# Hypnos_V2_1.net
KiCad netlist of a schematic drawn in EAGLE
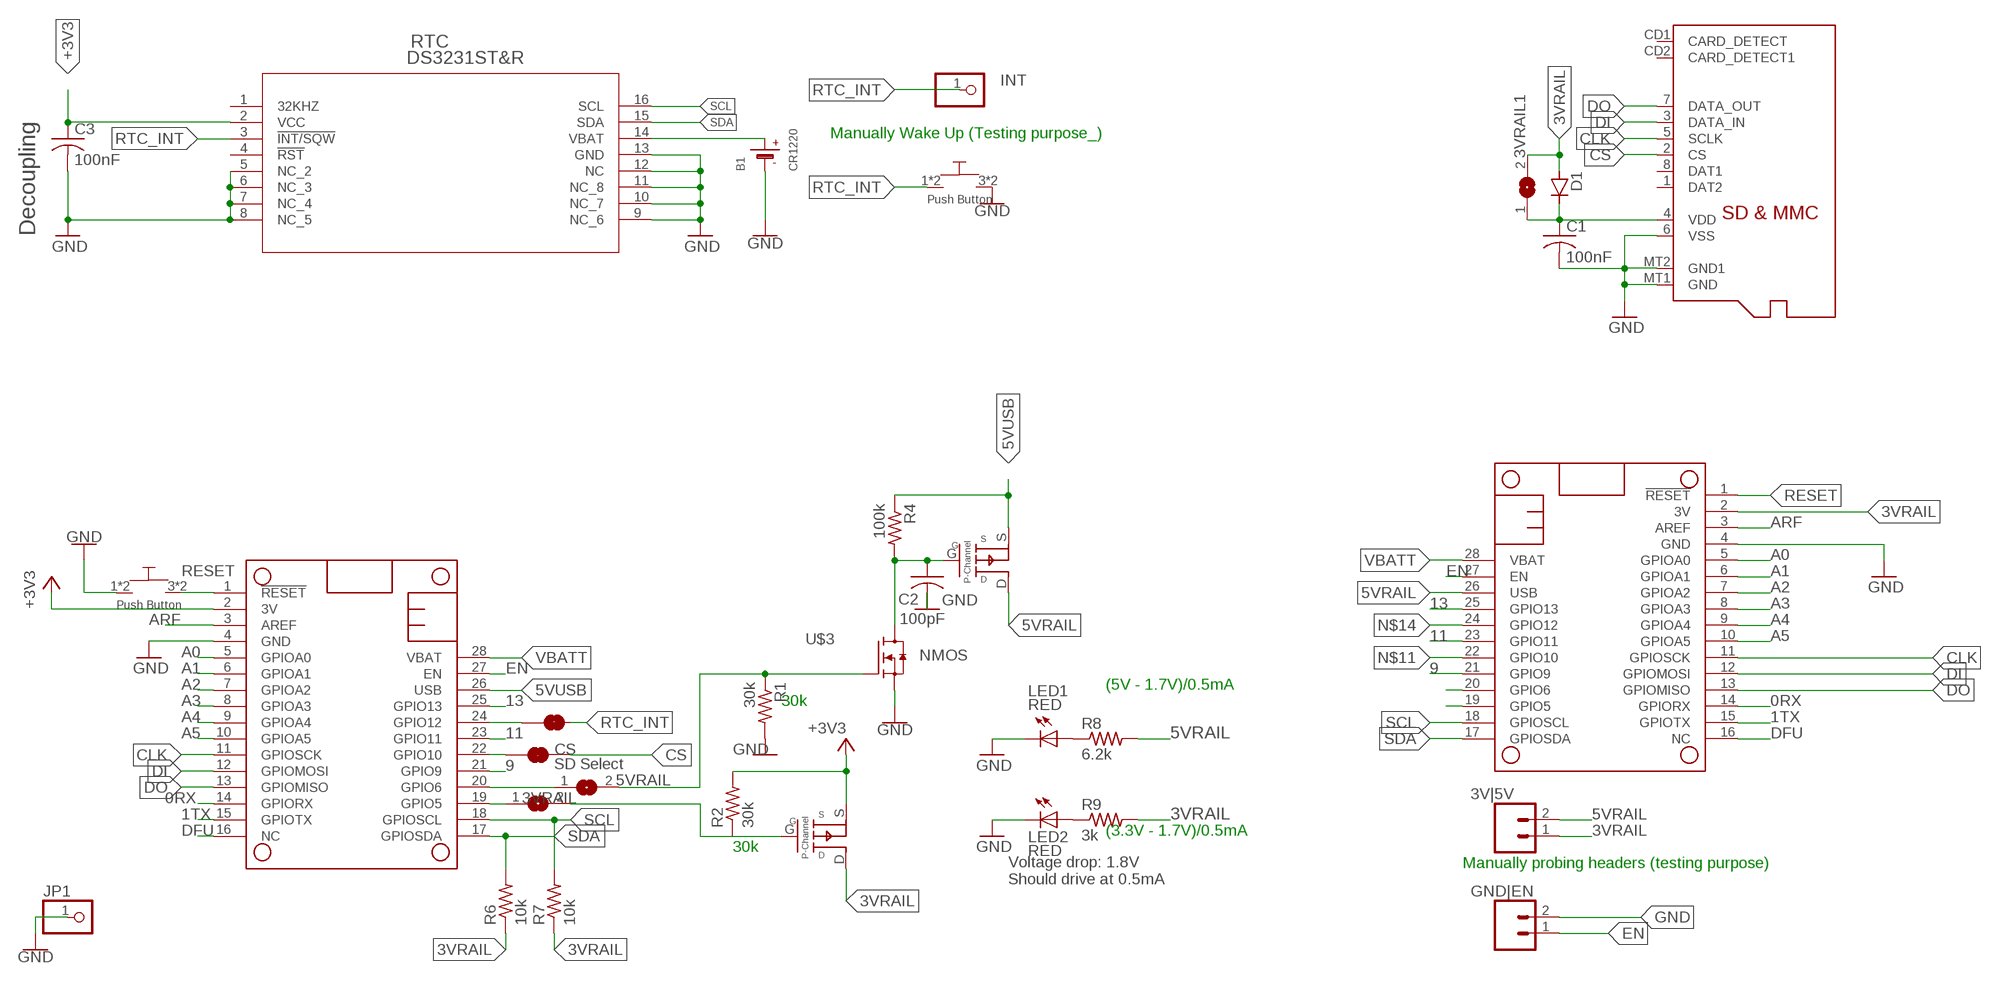
[diagram p0: schematic, sheet 1]

(export (version "E")
  (design (tool "Eeschema 10.0.6"))
  (components
    (comp (ref "3VRAIL")
      (value "SJ")
      (footprint "eagle-import:SJ")
      (libsource (lib "eagle-import") (part "SJ"))
    )
    (comp (ref "3VRAIL1")
      (value "SJ")
      (footprint "eagle-import:SJ")
      (libsource (lib "eagle-import") (part "SJ"))
    )
    (comp (ref "3V|5V")
      (value "CONN_021X02_NO_SILK")
      (footprint "eagle-import:1X02_NO_SILK")
      (libsource (lib "eagle-import") (part "CONN_021X02_NO_SILK"))
    )
    (comp (ref "5VRAIL")
      (value "SJ")
      (footprint "eagle-import:SJ")
      (libsource (lib "eagle-import") (part "SJ"))
    )
    (comp (ref "B1")
      (value "CR1220")
      (footprint "eagle-import:CR1220")
      (libsource (lib "eagle-import") (part "BATTERYCR1220_SMT"))
    )
    (comp (ref "C1")
      (value "100nF")
      (footprint "eagle-import:C1206")
      (libsource (lib "eagle-import") (part "C-USC1206"))
    )
    (comp (ref "C2")
      (value "100pF")
      (footprint "eagle-import:C0805")
      (libsource (lib "eagle-import") (part "C-USC0805"))
    )
    (comp (ref "C3")
      (value "100nF")
      (footprint "eagle-import:C1206")
      (libsource (lib "eagle-import") (part "C-USC1206"))
    )
    (comp (ref "CS")
      (value "SD Select")
      (footprint "eagle-import:SMT-JUMPER_2_NC_TRACE_SILK")
      (libsource (lib "eagle-import") (part "JUMPER-SMT_2_NC_TRACE_SILK"))
    )
    (comp (ref "D1")
      (value "D-SOD123")
      (footprint "eagle-import:SOD123")
      (libsource (lib "eagle-import") (part "D-SOD123"))
    )
    (comp (ref "GND|EN")
      (value "CONN_021X02_NO_SILK")
      (footprint "eagle-import:1X02_NO_SILK")
      (libsource (lib "eagle-import") (part "CONN_021X02_NO_SILK"))
    )
    (comp (ref "INT")
      (value "PINHD-1X1CB")
      (footprint "eagle-import:1X01-CLEANBIG")
      (libsource (lib "eagle-import") (part "PINHD-1X1CB"))
    )
    (comp (ref "JP1")
      (value "PINHD-1X1CB")
      (footprint "eagle-import:1X01-CLEANBIG")
      (libsource (lib "eagle-import") (part "PINHD-1X1CB"))
    )
    (comp (ref "LED1")
      (value "RED")
      (footprint "eagle-import:CHIPLED_0805")
      (libsource (lib "eagle-import") (part "LEDCHIPLED_0805"))
    )
    (comp (ref "LED2")
      (value "RED")
      (footprint "eagle-import:CHIPLED_0805")
      (libsource (lib "eagle-import") (part "LEDCHIPLED_0805"))
    )
    (comp (ref "MICROSD")
      (value "MICROSD")
      (footprint "eagle-import:MICROSD")
      (libsource (lib "eagle-import") (part "MICROSD"))
    )
    (comp (ref "MS1")
      (value "FEATHERWING")
      (footprint "eagle-import:FEATHERWING")
      (libsource (lib "eagle-import") (part "powerboard_FEATHERWING"))
    )
    (comp (ref "MS2")
      (value "FEATHERWING")
      (footprint "eagle-import:FEATHERWING")
      (libsource (lib "eagle-import") (part "FEATHERWING"))
    )
    (comp (ref "PMOS1")
      (value "SSM3J3228R")
      (footprint "eagle-import:SOT-23-3")
      (libsource (lib "eagle-import") (part "SSM3J3228R"))
    )
    (comp (ref "PMOS2")
      (value "SSM3J3228R")
      (footprint "eagle-import:SOT-23-3")
      (libsource (lib "eagle-import") (part "SSM3J3228R"))
    )
    (comp (ref "R1")
      (value "30k")
      (footprint "eagle-import:RES_1206")
      (fields
        (field (name "DIGIKEY_PART_NUMBER") "WSLP-.05TR-ND")
        (field (name "MANUFACTURER") "Vishay Dale")
        (field (name "MPN") "WSLP1206R0500FEA")
        (field (name "CREATED_BY") "PCBLayout.com")
      )
      (libsource (lib "eagle-import") (part "WSLP1206R0500FEA"))
    )
    (comp (ref "R2")
      (value "30k")
      (footprint "eagle-import:RES_1206")
      (fields
        (field (name "DIGIKEY_PART_NUMBER") "WSLP-.05TR-ND")
        (field (name "MANUFACTURER") "Vishay Dale")
        (field (name "MPN") "WSLP1206R0500FEA")
        (field (name "CREATED_BY") "PCBLayout.com")
      )
      (libsource (lib "eagle-import") (part "WSLP1206R0500FEA"))
    )
    (comp (ref "R4")
      (value "100k")
      (footprint "eagle-import:RES_1206")
      (fields
        (field (name "DIGIKEY_PART_NUMBER") "WSLP-.05TR-ND")
        (field (name "MANUFACTURER") "Vishay Dale")
        (field (name "MPN") "WSLP1206R0500FEA")
        (field (name "CREATED_BY") "PCBLayout.com")
      )
      (libsource (lib "eagle-import") (part "WSLP1206R0500FEA"))
    )
    (comp (ref "R6")
      (value "10k")
      (footprint "eagle-import:RES_1206")
      (fields
        (field (name "DIGIKEY_PART_NUMBER") "WSLP-.05TR-ND")
        (field (name "MANUFACTURER") "Vishay Dale")
        (field (name "MPN") "WSLP1206R0500FEA")
        (field (name "CREATED_BY") "PCBLayout.com")
      )
      (libsource (lib "eagle-import") (part "WSLP1206R0500FEA"))
    )
    (comp (ref "R7")
      (value "10k")
      (footprint "eagle-import:RES_1206")
      (fields
        (field (name "DIGIKEY_PART_NUMBER") "WSLP-.05TR-ND")
        (field (name "MANUFACTURER") "Vishay Dale")
        (field (name "MPN") "WSLP1206R0500FEA")
        (field (name "CREATED_BY") "PCBLayout.com")
      )
      (libsource (lib "eagle-import") (part "WSLP1206R0500FEA"))
    )
    (comp (ref "R8")
      (value "6.2k")
      (footprint "eagle-import:RES_1206")
      (fields
        (field (name "DIGIKEY_PART_NUMBER") "WSLP-.05TR-ND")
        (field (name "MANUFACTURER") "Vishay Dale")
        (field (name "MPN") "WSLP1206R0500FEA")
        (field (name "CREATED_BY") "PCBLayout.com")
      )
      (libsource (lib "eagle-import") (part "WSLP1206R0500FEA"))
    )
    (comp (ref "R9")
      (value "3k")
      (footprint "eagle-import:RES_1206")
      (fields
        (field (name "DIGIKEY_PART_NUMBER") "WSLP-.05TR-ND")
        (field (name "MANUFACTURER") "Vishay Dale")
        (field (name "MPN") "WSLP1206R0500FEA")
        (field (name "CREATED_BY") "PCBLayout.com")
      )
      (libsource (lib "eagle-import") (part "WSLP1206R0500FEA"))
    )
    (comp (ref "RTC")
      (value "DS3231ST&R")
      (footprint "eagle-import:21-0042B_16")
      (fields (field (name "MANUFACTURER_PART_NUMBER") "DS3231S#T&R"))
      (libsource (lib "eagle-import") (part "DS3231ST&R"))
    )
    (comp (ref "RTC_INT")
      (value "JUMPER-SMT_2_NC_TRACE_SILK")
      (footprint "eagle-import:SMT-JUMPER_2_NC_TRACE_SILK")
      (libsource (lib "eagle-import") (part "JUMPER-SMT_2_NC_TRACE_SILK"))
    )
    (comp (ref "U$1")
      (value "PUSH_BUTTON")
      (footprint "eagle-import:PUSHBUTTON_SMD")
      (libsource (lib "eagle-import") (part "PUSH_BUTTON"))
    )
    (comp (ref "U$2")
      (value "PUSH_BUTTON")
      (footprint "eagle-import:PUSHBUTTON_SMD")
      (libsource (lib "eagle-import") (part "PUSH_BUTTON"))
    )
    (comp (ref "U$3")
      (value "NMOS")
      (footprint "eagle-import:SOT23-S")
      (libsource (lib "eagle-import") (part "NMOS"))
    )
  )
  (nets
    (net (code "1") (name "+3V3") (class "Default")
      (node (ref "C3") (pin "1") (pinfunction "1_1") (pintype "passive"))
      (node (ref "MS2") (pin "2") (pinfunction "3V_2") (pintype "power_in"))
      (node (ref "PMOS2") (pin "S") (pinfunction "S_S") (pintype "bidirectional"))
      (node (ref "R2") (pin "2") (pinfunction "2_2") (pintype "passive"))
      (node (ref "RTC") (pin "2") (pinfunction "VCC_2") (pintype "power_in"))
    )
    (net (code "2") (name "/0RX") (class "Default")
      (node (ref "MS1") (pin "14") (pinfunction "GPIORX_14") (pintype "bidirectional"))
      (node (ref "MS2") (pin "14") (pinfunction "GPIORX_14") (pintype "bidirectional"))
    )
    (net (code "3") (name "/1TX") (class "Default")
      (node (ref "MS1") (pin "15") (pinfunction "GPIOTX_15") (pintype "bidirectional"))
      (node (ref "MS2") (pin "15") (pinfunction "GPIOTX_15") (pintype "bidirectional"))
    )
    (net (code "4") (name "/9") (class "Default")
      (node (ref "MS1") (pin "21") (pinfunction "GPIO9_21") (pintype "bidirectional"))
      (node (ref "MS2") (pin "21") (pinfunction "GPIO9_21") (pintype "bidirectional"))
    )
    (net (code "5") (name "/11") (class "Default")
      (node (ref "MS1") (pin "23") (pinfunction "GPIO11_23") (pintype "bidirectional"))
      (node (ref "MS2") (pin "23") (pinfunction "GPIO11_23") (pintype "bidirectional"))
    )
    (net (code "6") (name "/13") (class "Default")
      (node (ref "MS1") (pin "25") (pinfunction "GPIO13_25") (pintype "bidirectional"))
      (node (ref "MS2") (pin "25") (pinfunction "GPIO13_25") (pintype "bidirectional"))
    )
    (net (code "7") (name "/A0") (class "Default")
      (node (ref "MS1") (pin "5") (pinfunction "GPIOA0_5") (pintype "bidirectional"))
      (node (ref "MS2") (pin "5") (pinfunction "GPIOA0_5") (pintype "bidirectional"))
    )
    (net (code "8") (name "/A1") (class "Default")
      (node (ref "MS1") (pin "6") (pinfunction "GPIOA1_6") (pintype "bidirectional"))
      (node (ref "MS2") (pin "6") (pinfunction "GPIOA1_6") (pintype "bidirectional"))
    )
    (net (code "9") (name "/A2") (class "Default")
      (node (ref "MS1") (pin "7") (pinfunction "GPIOA2_7") (pintype "bidirectional"))
      (node (ref "MS2") (pin "7") (pinfunction "GPIOA2_7") (pintype "bidirectional"))
    )
    (net (code "10") (name "/A3") (class "Default")
      (node (ref "MS1") (pin "8") (pinfunction "GPIOA3_8") (pintype "bidirectional"))
      (node (ref "MS2") (pin "8") (pinfunction "GPIOA3_8") (pintype "bidirectional"))
    )
    (net (code "11") (name "/A4") (class "Default")
      (node (ref "MS1") (pin "9") (pinfunction "GPIOA4_9") (pintype "bidirectional"))
      (node (ref "MS2") (pin "9") (pinfunction "GPIOA4_9") (pintype "bidirectional"))
    )
    (net (code "12") (name "/A5") (class "Default")
      (node (ref "MS1") (pin "10") (pinfunction "GPIOA5_10") (pintype "bidirectional"))
      (node (ref "MS2") (pin "10") (pinfunction "GPIOA5_10") (pintype "bidirectional"))
    )
    (net (code "13") (name "/ARF") (class "Default")
      (node (ref "MS1") (pin "3") (pinfunction "AREF_3") (pintype "passive"))
      (node (ref "MS2") (pin "3") (pinfunction "AREF_3") (pintype "passive"))
    )
    (net (code "14") (name "/DFU") (class "Default")
      (node (ref "MS1") (pin "16") (pinfunction "NC_16") (pintype "passive"))
      (node (ref "MS2") (pin "16") (pinfunction "NC_16") (pintype "passive"))
    )
    (net (code "15") (name "3VRAIL") (class "Default")
      (node (ref "3VRAIL1") (pin "2") (pinfunction "2_2") (pintype "passive"))
      (node (ref "3V|5V") (pin "1") (pinfunction "1_1") (pintype "passive"))
      (node (ref "D1") (pin "2") (pinfunction "A_2") (pintype "passive"))
      (node (ref "MS1") (pin "2") (pinfunction "3V_2") (pintype "power_in"))
      (node (ref "PMOS2") (pin "D") (pinfunction "D_D") (pintype "bidirectional"))
      (node (ref "R6") (pin "1") (pinfunction "1_1") (pintype "passive"))
      (node (ref "R7") (pin "1") (pinfunction "1_1") (pintype "passive"))
      (node (ref "R9") (pin "2") (pinfunction "2_2") (pintype "passive"))
    )
    (net (code "16") (name "5VRAIL") (class "Default")
      (node (ref "3V|5V") (pin "2") (pinfunction "2_2") (pintype "passive"))
      (node (ref "MS1") (pin "26") (pinfunction "USB_26") (pintype "power_in"))
      (node (ref "PMOS1") (pin "D") (pinfunction "D_D") (pintype "bidirectional"))
      (node (ref "R8") (pin "2") (pinfunction "2_2") (pintype "passive"))
    )
    (net (code "17") (name "5VUSB") (class "Default")
      (node (ref "MS2") (pin "26") (pinfunction "USB_26") (pintype "power_in"))
      (node (ref "PMOS1") (pin "S") (pinfunction "S_S") (pintype "bidirectional"))
      (node (ref "R4") (pin "1") (pinfunction "1_1") (pintype "passive"))
    )
    (net (code "18") (name "CLK") (class "Default")
      (node (ref "MICROSD") (pin "5") (pinfunction "SCLK_5") (pintype "input"))
      (node (ref "MS1") (pin "11") (pinfunction "GPIOSCK_11") (pintype "bidirectional"))
      (node (ref "MS2") (pin "11") (pinfunction "GPIOSCK_11") (pintype "bidirectional"))
    )
    (net (code "19") (name "CS") (class "Default")
      (node (ref "CS") (pin "2") (pinfunction "2_2") (pintype "passive"))
      (node (ref "MICROSD") (pin "2") (pinfunction "CS_2") (pintype "input"))
    )
    (net (code "20") (name "DI") (class "Default")
      (node (ref "MICROSD") (pin "3") (pinfunction "DATA_IN_3") (pintype "input"))
      (node (ref "MS1") (pin "12") (pinfunction "GPIOMOSI_12") (pintype "bidirectional"))
      (node (ref "MS2") (pin "12") (pinfunction "GPIOMOSI_12") (pintype "bidirectional"))
    )
    (net (code "21") (name "DO") (class "Default")
      (node (ref "MICROSD") (pin "7") (pinfunction "DATA_OUT_7") (pintype "output"))
      (node (ref "MS1") (pin "13") (pinfunction "GPIOMISO_13") (pintype "bidirectional"))
      (node (ref "MS2") (pin "13") (pinfunction "GPIOMISO_13") (pintype "bidirectional"))
    )
    (net (code "22") (name "EN") (class "Default")
      (node (ref "GND|EN") (pin "1") (pinfunction "1_1") (pintype "passive"))
      (node (ref "MS1") (pin "27") (pinfunction "EN_27") (pintype "passive"))
      (node (ref "MS2") (pin "27") (pinfunction "EN_27") (pintype "passive"))
    )
    (net (code "23") (name "GND") (class "Default")
      (node (ref "B1") (pin "-") (pinfunction "-_-") (pintype "passive"))
      (node (ref "C1") (pin "2") (pinfunction "2_2") (pintype "passive"))
      (node (ref "C2") (pin "2") (pinfunction "2_2") (pintype "passive"))
      (node (ref "C3") (pin "2") (pinfunction "2_2") (pintype "passive"))
      (node (ref "GND|EN") (pin "2") (pinfunction "2_2") (pintype "passive"))
      (node (ref "JP1") (pin "1") (pinfunction "1_1") (pintype "passive"))
      (node (ref "LED1") (pin "C") (pinfunction "C_C") (pintype "passive"))
      (node (ref "LED2") (pin "C") (pinfunction "C_C") (pintype "passive"))
      (node (ref "MICROSD") (pin "6") (pinfunction "VSS_6") (pintype "power_in"))
      (node (ref "MICROSD") (pin "MT1") (pinfunction "GND_MT1") (pintype "power_in"))
      (node (ref "MICROSD") (pin "MT2") (pinfunction "GND1_MT2") (pintype "power_in"))
      (node (ref "MS1") (pin "4") (pinfunction "GND_4") (pintype "power_in"))
      (node (ref "MS2") (pin "4") (pinfunction "GND_4") (pintype "power_in"))
      (node (ref "R1") (pin "2") (pinfunction "2_2") (pintype "passive"))
      (node (ref "RTC") (pin "10") (pinfunction "NC_7_10") (pintype "passive"))
      (node (ref "RTC") (pin "11") (pinfunction "NC_8_11") (pintype "passive"))
      (node (ref "RTC") (pin "12") (pinfunction "NC_12") (pintype "passive"))
      (node (ref "RTC") (pin "13") (pinfunction "GND_13") (pintype "power_in"))
      (node (ref "RTC") (pin "5") (pinfunction "NC_2_5") (pintype "passive"))
      (node (ref "RTC") (pin "6") (pinfunction "NC_3_6") (pintype "passive"))
      (node (ref "RTC") (pin "7") (pinfunction "NC_4_7") (pintype "passive"))
      (node (ref "RTC") (pin "8") (pinfunction "NC_5_8") (pintype "passive"))
      (node (ref "RTC") (pin "9") (pinfunction "NC_6_9") (pintype "passive"))
      (node (ref "U$1") (pin "1") (pinfunction "P$1_1") (pintype "bidirectional"))
      (node (ref "U$1") (pin "2") (pinfunction "P$1_2") (pintype "bidirectional"))
      (node (ref "U$2") (pin "3") (pinfunction "P$2_3") (pintype "bidirectional"))
      (node (ref "U$2") (pin "4") (pinfunction "P$2_4") (pintype "bidirectional"))
      (node (ref "U$3") (pin "2") (pinfunction "S_2") (pintype "passive"))
    )
    (net (code "24") (name "N$11") (class "Default")
      (node (ref "CS") (pin "1") (pinfunction "1_1") (pintype "passive"))
      (node (ref "MS1") (pin "22") (pinfunction "GPIO10_22") (pintype "bidirectional"))
      (node (ref "MS2") (pin "22") (pinfunction "GPIO10_22") (pintype "bidirectional"))
    )
    (net (code "25") (name "N$14") (class "Default")
      (node (ref "MS1") (pin "24") (pinfunction "GPIO12_24") (pintype "bidirectional"))
      (node (ref "MS2") (pin "24") (pinfunction "GPIO12_24") (pintype "bidirectional"))
      (node (ref "RTC_INT") (pin "1") (pinfunction "1_1") (pintype "passive"))
    )
    (net (code "26") (name "Net-(3VRAIL-Pad2)") (class "Default")
      (node (ref "3VRAIL") (pin "2") (pinfunction "2_2") (pintype "passive"))
      (node (ref "PMOS2") (pin "G") (pinfunction "G_G") (pintype "bidirectional"))
      (node (ref "R2") (pin "1") (pinfunction "1_1") (pintype "passive"))
    )
    (net (code "27") (name "Net-(B1-+)") (class "Default")
      (node (ref "B1") (pin "+$1") (pinfunction "+_+$1") (pintype "passive"))
      (node (ref "RTC") (pin "14") (pinfunction "VBAT_14") (pintype "power_in"))
    )
    (net (code "28") (name "Net-(D1-C)") (class "Default")
      (node (ref "3VRAIL1") (pin "1") (pinfunction "1_1") (pintype "passive"))
      (node (ref "C1") (pin "1") (pinfunction "1_1") (pintype "passive"))
      (node (ref "D1") (pin "1") (pinfunction "C_1") (pintype "passive"))
      (node (ref "MICROSD") (pin "4") (pinfunction "VDD_4") (pintype "power_in"))
    )
    (net (code "29") (name "Net-(LED1-PadA)") (class "Default")
      (node (ref "LED1") (pin "A") (pinfunction "A_A") (pintype "passive"))
      (node (ref "R8") (pin "1") (pinfunction "1_1") (pintype "passive"))
    )
    (net (code "30") (name "Net-(LED2-PadA)") (class "Default")
      (node (ref "LED2") (pin "A") (pinfunction "A_A") (pintype "passive"))
      (node (ref "R9") (pin "1") (pinfunction "1_1") (pintype "passive"))
    )
    (net (code "31") (name "Net-(MS2-GPIO5)") (class "Default")
      (node (ref "3VRAIL") (pin "1") (pinfunction "1_1") (pintype "passive"))
      (node (ref "MS2") (pin "19") (pinfunction "GPIO5_19") (pintype "bidirectional"))
    )
    (net (code "32") (name "Net-(MS2-GPIO6)") (class "Default")
      (node (ref "5VRAIL") (pin "1") (pinfunction "1_1") (pintype "passive"))
      (node (ref "MS2") (pin "20") (pinfunction "GPIO6_20") (pintype "bidirectional"))
    )
    (net (code "33") (name "Net-(U$3-D)") (class "Default")
      (node (ref "C2") (pin "1") (pinfunction "1_1") (pintype "passive"))
      (node (ref "PMOS1") (pin "G") (pinfunction "G_G") (pintype "bidirectional"))
      (node (ref "R4") (pin "2") (pinfunction "2_2") (pintype "passive"))
      (node (ref "U$3") (pin "3") (pinfunction "D_3") (pintype "passive"))
    )
    (net (code "34") (name "Net-(U$3-G)") (class "Default")
      (node (ref "5VRAIL") (pin "2") (pinfunction "2_2") (pintype "passive"))
      (node (ref "R1") (pin "1") (pinfunction "1_1") (pintype "passive"))
      (node (ref "U$3") (pin "1") (pinfunction "G_1") (pintype "passive"))
    )
    (net (code "35") (name "RESET") (class "Default")
      (node (ref "MS1") (pin "1") (pinfunction "~{RESET}_1") (pintype "input"))
      (node (ref "MS2") (pin "1") (pinfunction "~{RESET}_1") (pintype "input"))
      (node (ref "U$1") (pin "3") (pinfunction "P$2_3") (pintype "bidirectional"))
      (node (ref "U$1") (pin "4") (pinfunction "P$2_4") (pintype "bidirectional"))
    )
    (net (code "36") (name "RTC_INT") (class "Default")
      (node (ref "INT") (pin "1") (pinfunction "1_1") (pintype "passive"))
      (node (ref "RTC") (pin "3") (pinfunction "~{INT/SQW}_3") (pintype "passive"))
      (node (ref "RTC_INT") (pin "2") (pinfunction "2_2") (pintype "passive"))
      (node (ref "U$2") (pin "1") (pinfunction "P$1_1") (pintype "bidirectional"))
      (node (ref "U$2") (pin "2") (pinfunction "P$1_2") (pintype "bidirectional"))
    )
    (net (code "37") (name "SCL") (class "Default")
      (node (ref "MS1") (pin "18") (pinfunction "GPIOSCL_18") (pintype "bidirectional"))
      (node (ref "MS2") (pin "18") (pinfunction "GPIOSCL_18") (pintype "bidirectional"))
      (node (ref "R7") (pin "2") (pinfunction "2_2") (pintype "passive"))
      (node (ref "RTC") (pin "16") (pinfunction "SCL_16") (pintype "passive"))
    )
    (net (code "38") (name "SDA") (class "Default")
      (node (ref "MS1") (pin "17") (pinfunction "GPIOSDA_17") (pintype "bidirectional"))
      (node (ref "MS2") (pin "17") (pinfunction "GPIOSDA_17") (pintype "bidirectional"))
      (node (ref "R6") (pin "2") (pinfunction "2_2") (pintype "passive"))
      (node (ref "RTC") (pin "15") (pinfunction "SDA_15") (pintype "passive"))
    )
    (net (code "39") (name "VBATT") (class "Default")
      (node (ref "MS1") (pin "28") (pinfunction "VBAT_28") (pintype "power_in"))
      (node (ref "MS2") (pin "28") (pinfunction "VBAT_28") (pintype "power_in"))
    )
    (net (code "40") (name "unconnected-(MICROSD-CARD_DETECT-PadCD1)") (class "Default")
      (node (ref "MICROSD") (pin "CD1") (pinfunction "CARD_DETECT_CD1") (pintype "passive"))
    )
    (net (code "41") (name "unconnected-(MICROSD-CARD_DETECT1-PadCD2)") (class "Default")
      (node (ref "MICROSD") (pin "CD2") (pinfunction "CARD_DETECT1_CD2") (pintype "passive"))
    )
    (net (code "42") (name "unconnected-(MICROSD-DAT1-Pad8)") (class "Default")
      (node (ref "MICROSD") (pin "8") (pinfunction "DAT1_8") (pintype "bidirectional"))
    )
    (net (code "43") (name "unconnected-(MICROSD-DAT2-Pad1)") (class "Default")
      (node (ref "MICROSD") (pin "1") (pinfunction "DAT2_1") (pintype "bidirectional"))
    )
    (net (code "44") (name "unconnected-(MS1-GPIO5-Pad19)") (class "Default")
      (node (ref "MS1") (pin "19") (pinfunction "GPIO5_19") (pintype "bidirectional"))
    )
    (net (code "45") (name "unconnected-(MS1-GPIO6-Pad20)") (class "Default")
      (node (ref "MS1") (pin "20") (pinfunction "GPIO6_20") (pintype "bidirectional"))
    )
    (net (code "46") (name "unconnected-(RTC-32KHZ-Pad1)") (class "Default")
      (node (ref "RTC") (pin "1") (pinfunction "32KHZ_1") (pintype "passive"))
    )
    (net (code "47") (name "unconnected-(RTC-~{RST}-Pad4)") (class "Default")
      (node (ref "RTC") (pin "4") (pinfunction "~{RST}_4") (pintype "passive"))
    )
  )
)
